# ESP-Interface.net
KiCad netlist of a schematic drawn in Altium Designer
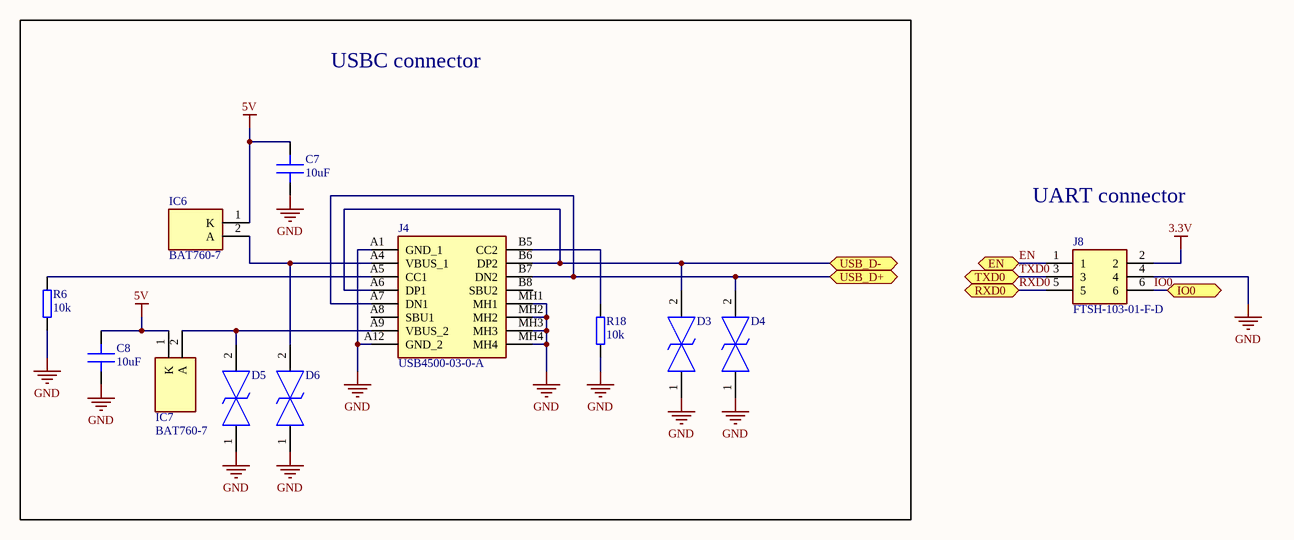
[diagram p0: ESP-Interface.SchDoc]

(export (version "E")
  (design (tool "Eeschema 10.0.6"))
  (components
    (comp (ref "C7")
      (value "10uF")
      (footprint "C 0402")
      (description "MLCC Capacitor")
      (libsource (lib "Components") (part "Capacitor"))
    )
    (comp (ref "C8")
      (value "10uF")
      (footprint "C 0402")
      (description "MLCC Capacitor")
      (libsource (lib "Components") (part "Capacitor"))
    )
    (comp (ref "D3")
      (value "LESD5D5.0CT1G")
      (footprint "SamacSys:LESD5D50CT1G")
      (description "TVS Diode (Bi-directional)")
      (libsource (lib "caravan_sch_lib") (part "LESD5D5.0CT1G"))
    )
    (comp (ref "D4")
      (value "LESD5D5.0CT1G")
      (footprint "SamacSys:LESD5D50CT1G")
      (description "TVS Diode (Bi-directional)")
      (libsource (lib "caravan_sch_lib") (part "LESD5D5.0CT1G"))
    )
    (comp (ref "D5")
      (value "LESD5D5.0CT1G")
      (footprint "SamacSys:LESD5D50CT1G")
      (description "TVS Diode (Bi-directional)")
      (libsource (lib "caravan_sch_lib") (part "LESD5D5.0CT1G"))
    )
    (comp (ref "D6")
      (value "LESD5D5.0CT1G")
      (footprint "SamacSys:LESD5D50CT1G")
      (description "TVS Diode (Bi-directional)")
      (libsource (lib "caravan_sch_lib") (part "LESD5D5.0CT1G"))
    )
    (comp (ref "IC6")
      (value "BAT760-7")
      (footprint "SamacSys:SOD2513X120N")
      (description "Integrated Circuit")
      (libsource (lib "caravan_sch_lib") (part "BAT760-7"))
    )
    (comp (ref "IC7")
      (value "BAT760-7")
      (footprint "SamacSys:SOD2513X120N")
      (description "Integrated Circuit")
      (libsource (lib "") (part "BAT760-7_1"))
    )
    (comp (ref "J4")
      (value "USB4500-03-0-A")
      (footprint "SamacSys:USB4500030A")
      (description "Connector")
      (fields (field (name "MOUSER PART NUMBER") "640-USB4500030A"))
      (libsource (lib "caravan_sch_lib") (part "USB4500-03-0-A"))
    )
    (comp (ref "J8")
      (value "FTSH-103-01-F-D")
      (footprint "SamacSys:FTSH-103-XX-YYY-D")
      (description "Connector")
      (fields (field (name "MOUSER PART NUMBER") "200-FTSH10301FD"))
      (libsource (lib "*") (part "FTSH-103-01-F-D"))
    )
    (comp (ref "R6")
      (value "10k")
      (footprint "R 0402")
      (description "General pourpouse resistor")
      (libsource (lib "Components") (part "Resistor"))
    )
    (comp (ref "R18")
      (value "10k")
      (footprint "R 0402")
      (description "General pourpouse resistor")
      (libsource (lib "Components") (part "Resistor"))
    )
  )
  (nets
    (net (code "1") (name "/EN") (class "Default")
      (node (ref "J8") (pin "1") (pinfunction "1_1") (pintype "passive"))
    )
    (net (code "2") (name "/IO0") (class "Default")
      (node (ref "J8") (pin "6") (pinfunction "6_6") (pintype "passive"))
    )
    (net (code "3") (name "/RXD0") (class "Default")
      (node (ref "J8") (pin "5") (pinfunction "5_5") (pintype "passive"))
    )
    (net (code "4") (name "/TXD0") (class "Default")
      (node (ref "J8") (pin "3") (pinfunction "3_3") (pintype "passive"))
    )
    (net (code "5") (name "/USB_D+") (class "Default")
      (node (ref "D4") (pin "2") (pinfunction "2_2") (pintype "passive"))
      (node (ref "J4") (pin "A7") (pinfunction "DN1_A7") (pintype "passive"))
      (node (ref "J4") (pin "B7") (pinfunction "DN2_B7") (pintype "passive"))
    )
    (net (code "6") (name "/USB_D-") (class "Default")
      (node (ref "D3") (pin "2") (pinfunction "2_2") (pintype "passive"))
      (node (ref "J4") (pin "A6") (pinfunction "DP1_A6") (pintype "passive"))
      (node (ref "J4") (pin "B6") (pinfunction "DP2_B6") (pintype "passive"))
    )
    (net (code "7") (name "3.3V") (class "Default")
      (node (ref "J8") (pin "2") (pinfunction "2_2") (pintype "passive"))
    )
    (net (code "8") (name "5V") (class "Default")
      (node (ref "C7") (pin "1") (pinfunction "1_1") (pintype "passive"))
      (node (ref "C8") (pin "1") (pinfunction "1_1") (pintype "passive"))
      (node (ref "IC6") (pin "1") (pinfunction "K_1") (pintype "passive"))
      (node (ref "IC7") (pin "1") (pinfunction "K_1") (pintype "passive"))
    )
    (net (code "9") (name "GND") (class "Default")
      (node (ref "C7") (pin "2") (pinfunction "2_2") (pintype "passive"))
      (node (ref "C8") (pin "2") (pinfunction "2_2") (pintype "passive"))
      (node (ref "D3") (pin "1") (pinfunction "1_1") (pintype "passive"))
      (node (ref "D4") (pin "1") (pinfunction "1_1") (pintype "passive"))
      (node (ref "D5") (pin "1") (pinfunction "1_1") (pintype "passive"))
      (node (ref "D6") (pin "1") (pinfunction "1_1") (pintype "passive"))
      (node (ref "J4") (pin "A1") (pinfunction "GND_1_A1") (pintype "passive"))
      (node (ref "J4") (pin "A12") (pinfunction "GND_2_A12") (pintype "passive"))
      (node (ref "J4") (pin "MH1") (pinfunction "MH1_MH1") (pintype "passive"))
      (node (ref "J4") (pin "MH2") (pinfunction "MH2_MH2") (pintype "passive"))
      (node (ref "J4") (pin "MH3") (pinfunction "MH3_MH3") (pintype "passive"))
      (node (ref "J4") (pin "MH4") (pinfunction "MH4_MH4") (pintype "passive"))
      (node (ref "J8") (pin "4") (pinfunction "4_4") (pintype "passive"))
      (node (ref "R18") (pin "1") (pinfunction "1_1") (pintype "passive"))
      (node (ref "R6") (pin "1") (pinfunction "1_1") (pintype "passive"))
    )
    (net (code "10") (name "Net-(IC6-A)") (class "Default")
      (node (ref "D6") (pin "2") (pinfunction "2_2") (pintype "passive"))
      (node (ref "IC6") (pin "2") (pinfunction "A_2") (pintype "passive"))
      (node (ref "J4") (pin "A4") (pinfunction "VBUS_1_A4") (pintype "passive"))
    )
    (net (code "11") (name "Net-(IC7-A)") (class "Default")
      (node (ref "D5") (pin "2") (pinfunction "2_2") (pintype "passive"))
      (node (ref "IC7") (pin "2") (pinfunction "A_2") (pintype "passive"))
      (node (ref "J4") (pin "A9") (pinfunction "VBUS_2_A9") (pintype "passive"))
    )
    (net (code "12") (name "Net-(J4-CC1)") (class "Default")
      (node (ref "J4") (pin "A5") (pinfunction "CC1_A5") (pintype "passive"))
      (node (ref "R6") (pin "2") (pinfunction "2_2") (pintype "passive"))
    )
    (net (code "13") (name "Net-(J4-CC2)") (class "Default")
      (node (ref "J4") (pin "B5") (pinfunction "CC2_B5") (pintype "passive"))
      (node (ref "R18") (pin "2") (pinfunction "2_2") (pintype "passive"))
    )
    (net (code "14") (name "unconnected-(J4-SBU1-PadA8)") (class "Default")
      (node (ref "J4") (pin "A8") (pinfunction "SBU1_A8") (pintype "passive"))
    )
    (net (code "15") (name "unconnected-(J4-SBU2-PadB8)") (class "Default")
      (node (ref "J4") (pin "B8") (pinfunction "SBU2_B8") (pintype "passive"))
    )
  )
)
